# cell.net
KiCad netlist of a schematic drawn in EAGLE
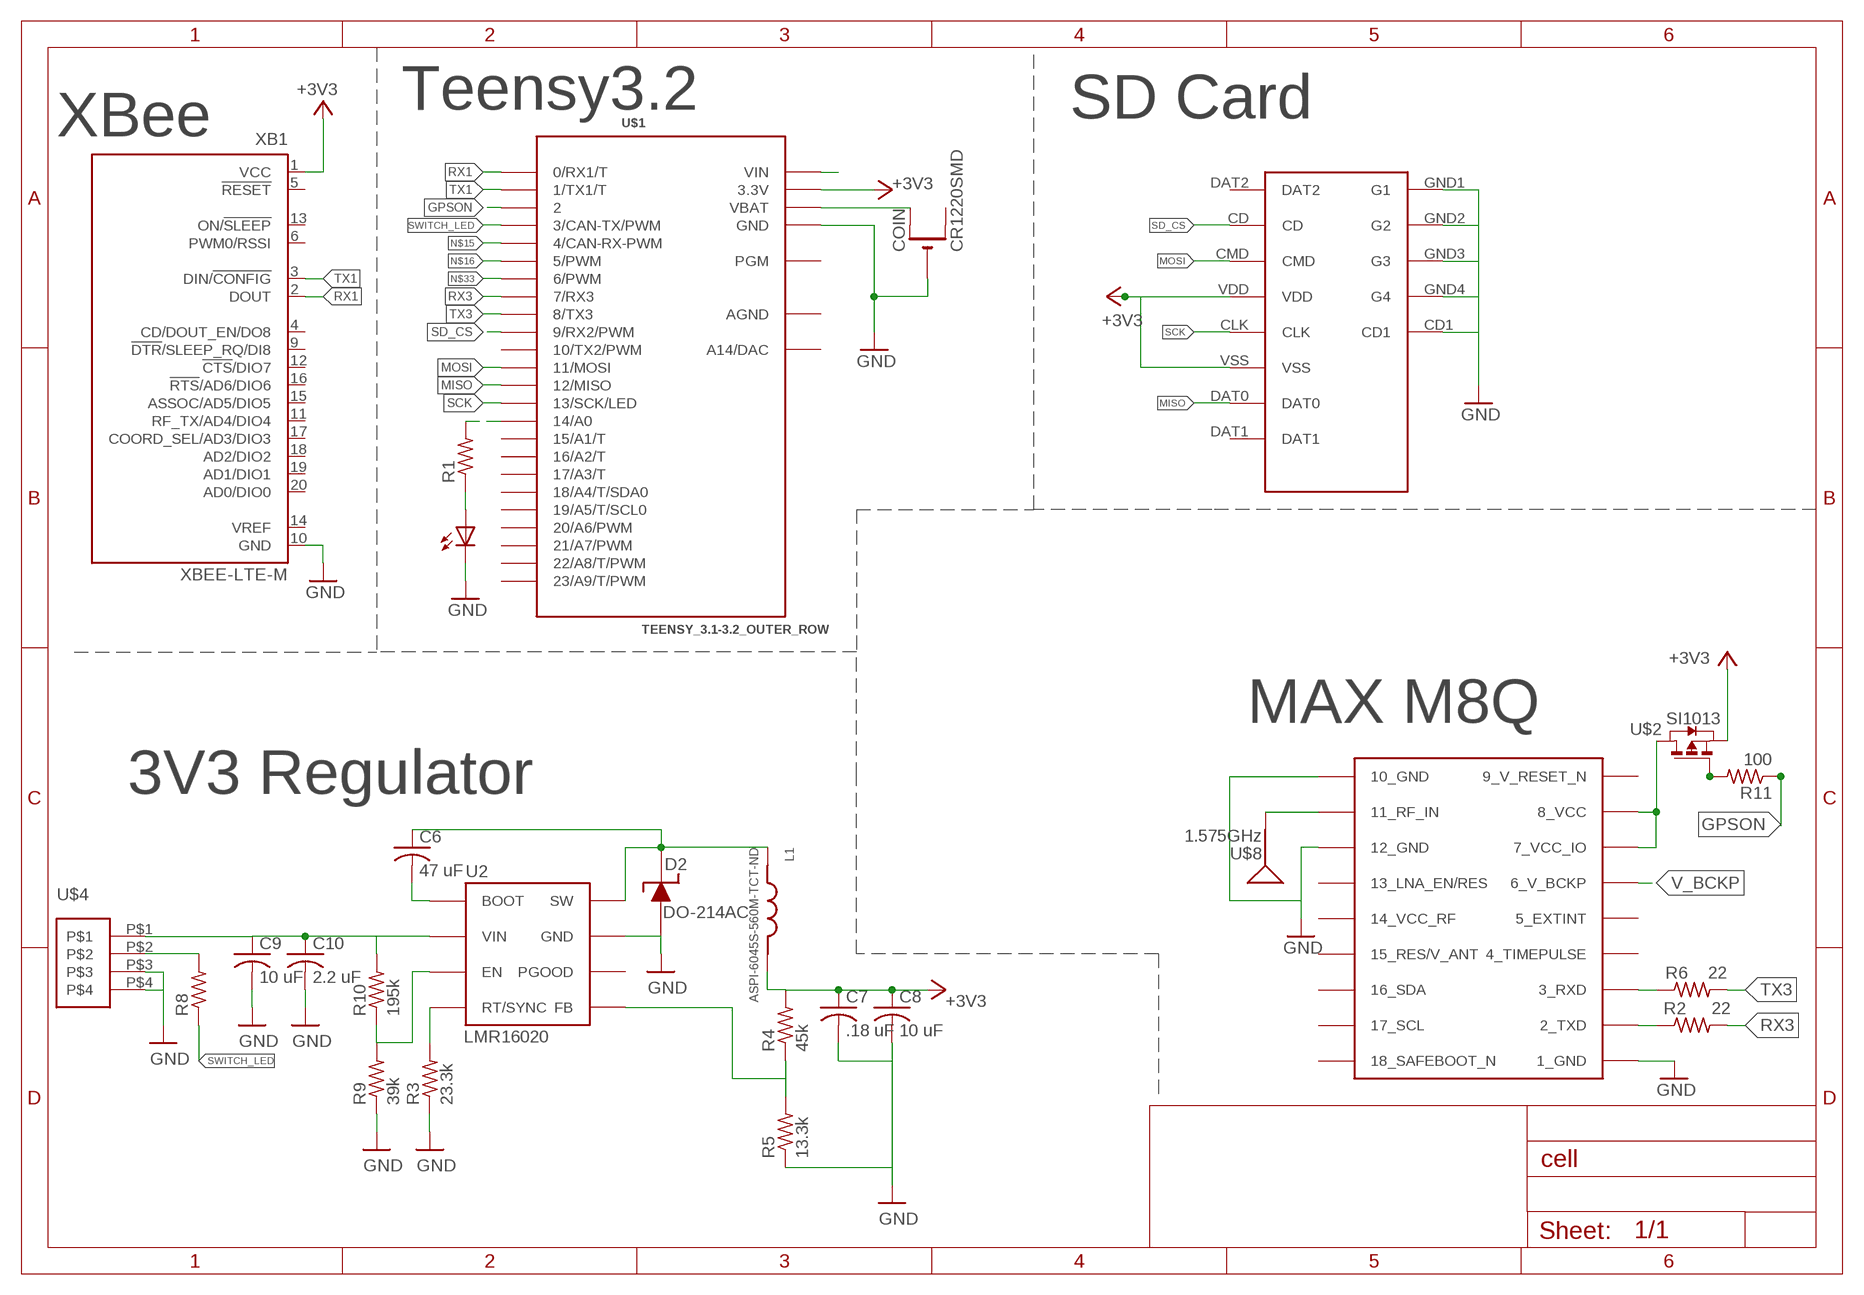
[diagram p0: schematic, sheet 1]

(export (version "E")
  (design (tool "Eeschema 10.0.6"))
  (components
    (comp (ref "C6")
      (value "47 uF")
      (footprint "eagle-import:C0805")
      (libsource (lib "eagle-import") (part "C-USC0805"))
    )
    (comp (ref "C7")
      (value ".18 uF")
      (footprint "eagle-import:C0603")
      (libsource (lib "eagle-import") (part "C-USC0603"))
    )
    (comp (ref "C8")
      (value "10 uF")
      (footprint "eagle-import:C0603")
      (libsource (lib "eagle-import") (part "C-USC0603"))
    )
    (comp (ref "C9")
      (value "10 uF")
      (footprint "eagle-import:C1210")
      (libsource (lib "eagle-import") (part "C-USC1210"))
    )
    (comp (ref "C10")
      (value "2.2 uF")
      (footprint "eagle-import:C1210")
      (libsource (lib "eagle-import") (part "C-USC1210"))
    )
    (comp (ref "COIN")
      (value "CR1220SMD")
      (footprint "eagle-import:CR1220-SMD")
      (libsource (lib "eagle-import") (part "CR1220SMT"))
    )
    (comp (ref "D2")
      (value "DO-214AC")
      (footprint "eagle-import:DO-214AC")
      (libsource (lib "eagle-import") (part "DO-214AC"))
    )
    (comp (ref "L1")
      (value "ASPI-6045S-560M-TCT-ND")
      (footprint "eagle-import:ABRACON")
      (libsource (lib "eagle-import") (part "ASPI-6045S-560M-TCT-ND"))
    )
    (comp (ref "LED1")
      (value "Green")
      (footprint "eagle-import:CHIP-LED0603")
      (libsource (lib "eagle-import") (part "LEDCHIP-LED0603"))
    )
    (comp (ref "R1")
      (value "470")
      (footprint "eagle-import:R0603")
      (libsource (lib "eagle-import") (part "resistor_R-US_R0603"))
    )
    (comp (ref "R2")
      (value "22")
      (footprint "eagle-import:R0603")
      (libsource (lib "eagle-import") (part "R-US_R0603"))
    )
    (comp (ref "R3")
      (value "23.3k")
      (footprint "eagle-import:R0603")
      (libsource (lib "eagle-import") (part "resistor_R-US_R0603"))
    )
    (comp (ref "R4")
      (value "45k")
      (footprint "eagle-import:R0603")
      (libsource (lib "eagle-import") (part "resistor_R-US_R0603"))
    )
    (comp (ref "R5")
      (value "13.3k")
      (footprint "eagle-import:R0603")
      (libsource (lib "eagle-import") (part "resistor_R-US_R0603"))
    )
    (comp (ref "R6")
      (value "22")
      (footprint "eagle-import:R0603")
      (libsource (lib "eagle-import") (part "R-US_R0603"))
    )
    (comp (ref "R8")
      (value "R-US_R0603")
      (footprint "eagle-import:R0603")
      (libsource (lib "eagle-import") (part "resistor_R-US_R0603"))
    )
    (comp (ref "R9")
      (value "39k")
      (footprint "eagle-import:R0603")
      (libsource (lib "eagle-import") (part "resistor_R-US_R0603"))
    )
    (comp (ref "R10")
      (value "195k")
      (footprint "eagle-import:R0603")
      (libsource (lib "eagle-import") (part "resistor_R-US_R0603"))
    )
    (comp (ref "R11")
      (value "100")
      (footprint "eagle-import:R0603")
      (libsource (lib "eagle-import") (part "R-US_R0603"))
    )
    (comp (ref "U$1")
      (value "TEENSY_3.1-3.2_OUTER_ROW")
      (footprint "eagle-import:TEENSY_3.0-3.2&LC_OUTER_ROW")
      (libsource (lib "eagle-import") (part "TEENSY_3.1-3.2_OUTER_ROW"))
    )
    (comp (ref "U$2")
      (value "SI1013")
      (footprint "eagle-import:SC-75")
      (libsource (lib "eagle-import") (part "SI1013"))
    )
    (comp (ref "U$3")
      (value "MICRO_SD")
      (footprint "eagle-import:MICRO_SD_HINGED")
      (libsource (lib "eagle-import") (part "MICRO_SD"))
    )
    (comp (ref "U$4")
      (value "MICROCLASP_4")
      (footprint "eagle-import:4_PIN_MICROCLASP")
      (libsource (lib "eagle-import") (part "MICROCLASP_4"))
    )
    (comp (ref "U$7")
      (value "MAX-M8")
      (footprint "eagle-import:MAX-M8")
      (libsource (lib "eagle-import") (part "MAX-M8"))
    )
    (comp (ref "U$8")
      (value "1.575GHz")
      (footprint "eagle-import:SPARKFUN-GPS_ANT-GPS-2X7MM")
      (libsource (lib "eagle-import") (part "SPARKFUN-GPS_ANTENNAGPS-2X7MM"))
    )
    (comp (ref "U2")
      (value "LMR16020")
      (footprint "eagle-import:SO8")
      (libsource (lib "eagle-import") (part "LMR16020"))
    )
    (comp (ref "XB1")
      (value "XBEE-LTE-M")
      (footprint "eagle-import:XBEE-PRO")
      (fields (field (name "MPN") "XBP24-AWI-001"))
      (libsource (lib "eagle-import") (part "XBEE-PRO"))
    )
  )
  (nets
    (net (code "1") (name "+3V3") (class "Default")
      (node (ref "C7") (pin "1") (pinfunction "1_1") (pintype "passive"))
      (node (ref "C8") (pin "1") (pinfunction "1_1") (pintype "passive"))
      (node (ref "L1") (pin "P$2") (pinfunction "P$2_P$2") (pintype "bidirectional"))
      (node (ref "R4") (pin "2") (pinfunction "2_2") (pintype "passive"))
      (node (ref "U$1") (pin "3.3V") (pinfunction "3.3V_3.3V") (pintype "power_in"))
      (node (ref "U$1") (pin "3.3V1") (pinfunction "3.3V_3.3V1") (pintype "power_in"))
      (node (ref "U$2") (pin "P$2") (pinfunction "S_P$2") (pintype "passive"))
      (node (ref "U$3") (pin "VDD") (pinfunction "VDD_VDD") (pintype "bidirectional"))
      (node (ref "U$3") (pin "VSS") (pinfunction "VSS_VSS") (pintype "bidirectional"))
      (node (ref "XB1") (pin "1") (pinfunction "VCC_1") (pintype "power_in"))
    )
    (net (code "2") (name "/9_V_RESET_N") (class "Default")
      (node (ref "U$7") (pin "9_RESET_N") (pinfunction "9_V_RESET_N_9_RESET_N") (pintype "power_in"))
    )
    (net (code "3") (name "/AGND") (class "Default")
      (node (ref "U$1") (pin "AGND") (pinfunction "AGND_AGND") (pintype "power_in"))
    )
    (net (code "4") (name "GND") (class "Default")
      (node (ref "C10") (pin "2") (pinfunction "2_2") (pintype "passive"))
      (node (ref "C7") (pin "2") (pinfunction "2_2") (pintype "passive"))
      (node (ref "C8") (pin "2") (pinfunction "2_2") (pintype "passive"))
      (node (ref "C9") (pin "2") (pinfunction "2_2") (pintype "passive"))
      (node (ref "COIN") (pin "-") (pinfunction "-_-") (pintype "passive"))
      (node (ref "D2") (pin "P$1") (pinfunction "P$1_P$1") (pintype "bidirectional"))
      (node (ref "LED1") (pin "C") (pinfunction "C_C") (pintype "passive"))
      (node (ref "R3") (pin "1") (pinfunction "1_1") (pintype "passive"))
      (node (ref "R5") (pin "1") (pinfunction "1_1") (pintype "passive"))
      (node (ref "R9") (pin "1") (pinfunction "1_1") (pintype "passive"))
      (node (ref "U$1") (pin "GND") (pinfunction "GND_GND") (pintype "power_in"))
      (node (ref "U$1") (pin "GND1") (pinfunction "GND_GND1") (pintype "power_in"))
      (node (ref "U$3") (pin "CD1") (pinfunction "CD1_CD1") (pintype "bidirectional"))
      (node (ref "U$3") (pin "GND1") (pinfunction "G1_GND1") (pintype "bidirectional"))
      (node (ref "U$3") (pin "GND2") (pinfunction "G2_GND2") (pintype "bidirectional"))
      (node (ref "U$3") (pin "GND3") (pinfunction "G3_GND3") (pintype "bidirectional"))
      (node (ref "U$3") (pin "GND4") (pinfunction "G4_GND4") (pintype "bidirectional"))
      (node (ref "U$4") (pin "P$3") (pinfunction "P$3_P$3") (pintype "bidirectional"))
      (node (ref "U$4") (pin "P$4") (pinfunction "P$4_P$4") (pintype "bidirectional"))
      (node (ref "U$7") (pin "10_GND") (pinfunction "10_GND_10_GND") (pintype "power_in"))
      (node (ref "U$7") (pin "12_GND") (pinfunction "12_GND_12_GND") (pintype "power_in"))
      (node (ref "U$7") (pin "1_GND") (pinfunction "1_GND_1_GND") (pintype "power_in"))
      (node (ref "U2") (pin "P$7") (pinfunction "GND_P$7") (pintype "bidirectional"))
      (node (ref "U2") (pin "PAD") (pinfunction "GND_PAD") (pintype "bidirectional"))
      (node (ref "XB1") (pin "10") (pinfunction "GND_10") (pintype "power_in"))
    )
    (net (code "5") (name "GPSON") (class "Default")
      (node (ref "R11") (pin "1") (pinfunction "1_1") (pintype "passive"))
      (node (ref "U$1") (pin "2") (pinfunction "2_2") (pintype "bidirectional"))
    )
    (net (code "6") (name "MISO") (class "Default")
      (node (ref "U$1") (pin "12") (pinfunction "12/MISO_12") (pintype "bidirectional"))
      (node (ref "U$3") (pin "DAT0") (pinfunction "DAT0_DAT0") (pintype "bidirectional"))
    )
    (net (code "7") (name "MOSI") (class "Default")
      (node (ref "U$1") (pin "11") (pinfunction "11/MOSI_11") (pintype "bidirectional"))
      (node (ref "U$3") (pin "CMD") (pinfunction "CMD_CMD") (pintype "bidirectional"))
    )
    (net (code "8") (name "N$15") (class "Default")
      (node (ref "U$1") (pin "4") (pinfunction "4/CAN-RX-PWM_4") (pintype "bidirectional"))
    )
    (net (code "9") (name "N$16") (class "Default")
      (node (ref "U$1") (pin "5") (pinfunction "5/PWM_5") (pintype "bidirectional"))
    )
    (net (code "10") (name "N$33") (class "Default")
      (node (ref "U$1") (pin "6") (pinfunction "6/PWM_6") (pintype "bidirectional"))
    )
    (net (code "11") (name "Net-(LED1-PadA)") (class "Default")
      (node (ref "LED1") (pin "A") (pinfunction "A_A") (pintype "passive"))
      (node (ref "R1") (pin "1") (pinfunction "1_1") (pintype "passive"))
    )
    (net (code "12") (name "Net-(R1-Pad2)") (class "Default")
      (node (ref "R1") (pin "2") (pinfunction "2_2") (pintype "passive"))
      (node (ref "U$1") (pin "14/A0") (pinfunction "14/A0_14/A0") (pintype "bidirectional"))
    )
    (net (code "13") (name "Net-(R2-Pad1)") (class "Default")
      (node (ref "R2") (pin "1") (pinfunction "1_1") (pintype "passive"))
      (node (ref "U$7") (pin "2_TXD") (pinfunction "2_TXD_2_TXD") (pintype "bidirectional"))
    )
    (net (code "14") (name "Net-(R6-Pad1)") (class "Default")
      (node (ref "R6") (pin "1") (pinfunction "1_1") (pintype "passive"))
      (node (ref "U$7") (pin "3_RXD") (pinfunction "3_RXD_3_RXD") (pintype "bidirectional"))
    )
    (net (code "15") (name "Net-(R8-Pad2)") (class "Default")
      (node (ref "R8") (pin "2") (pinfunction "2_2") (pintype "passive"))
      (node (ref "U$4") (pin "P$2") (pinfunction "P$2_P$2") (pintype "bidirectional"))
    )
    (net (code "16") (name "Net-(U$2-D)") (class "Default")
      (node (ref "U$2") (pin "P$3") (pinfunction "D_P$3") (pintype "passive"))
      (node (ref "U$7") (pin "7_VCC_IO") (pinfunction "7_VCC_IO_7_VCC_IO") (pintype "power_in"))
      (node (ref "U$7") (pin "8_VCC") (pinfunction "8_VCC_8_VCC") (pintype "power_in"))
    )
    (net (code "17") (name "Net-(U$2-G)") (class "Default")
      (node (ref "R11") (pin "2") (pinfunction "2_2") (pintype "passive"))
      (node (ref "U$2") (pin "P$1") (pinfunction "G_P$1") (pintype "passive"))
    )
    (net (code "18") (name "Net-(U$8-SIGNAL)") (class "Default")
      (node (ref "U$7") (pin "11_RF_IN") (pinfunction "11_RF_IN_11_RF_IN") (pintype "bidirectional"))
      (node (ref "U$8") (pin "1") (pinfunction "SIGNAL_1") (pintype "bidirectional"))
    )
    (net (code "19") (name "Net-(U2-BOOT)") (class "Default")
      (node (ref "C6") (pin "2") (pinfunction "2_2") (pintype "passive"))
      (node (ref "U2") (pin "P$1") (pinfunction "BOOT_P$1") (pintype "bidirectional"))
    )
    (net (code "20") (name "Net-(U2-EN)") (class "Default")
      (node (ref "R10") (pin "1") (pinfunction "1_1") (pintype "passive"))
      (node (ref "R9") (pin "2") (pinfunction "2_2") (pintype "passive"))
      (node (ref "U2") (pin "P$3") (pinfunction "EN_P$3") (pintype "bidirectional"))
    )
    (net (code "21") (name "Net-(U2-FB)") (class "Default")
      (node (ref "R4") (pin "1") (pinfunction "1_1") (pintype "passive"))
      (node (ref "R5") (pin "2") (pinfunction "2_2") (pintype "passive"))
      (node (ref "U2") (pin "P$5") (pinfunction "FB_P$5") (pintype "bidirectional"))
    )
    (net (code "22") (name "Net-(U2-RT{slash}SYNC)") (class "Default")
      (node (ref "R3") (pin "2") (pinfunction "2_2") (pintype "passive"))
      (node (ref "U2") (pin "P$4") (pinfunction "RT/SYNC_P$4") (pintype "bidirectional"))
    )
    (net (code "23") (name "Net-(U2-SW)") (class "Default")
      (node (ref "C6") (pin "1") (pinfunction "1_1") (pintype "passive"))
      (node (ref "D2") (pin "P$2") (pinfunction "P$2_P$2") (pintype "bidirectional"))
      (node (ref "L1") (pin "P$1") (pinfunction "P$1_P$1") (pintype "bidirectional"))
      (node (ref "U2") (pin "P$8") (pinfunction "SW_P$8") (pintype "bidirectional"))
    )
    (net (code "24") (name "Net-(U2-VIN)") (class "Default")
      (node (ref "C10") (pin "1") (pinfunction "1_1") (pintype "passive"))
      (node (ref "C9") (pin "1") (pinfunction "1_1") (pintype "passive"))
      (node (ref "R10") (pin "2") (pinfunction "2_2") (pintype "passive"))
      (node (ref "U$4") (pin "P$1") (pinfunction "P$1_P$1") (pintype "bidirectional"))
      (node (ref "U2") (pin "P$2") (pinfunction "VIN_P$2") (pintype "bidirectional"))
    )
    (net (code "25") (name "RX1") (class "Default")
      (node (ref "U$1") (pin "0") (pinfunction "0/RX1/T_0") (pintype "bidirectional"))
      (node (ref "XB1") (pin "2") (pinfunction "DOUT_2") (pintype "output"))
    )
    (net (code "26") (name "RX3") (class "Default")
      (node (ref "R2") (pin "2") (pinfunction "2_2") (pintype "passive"))
      (node (ref "U$1") (pin "7") (pinfunction "7/RX3_7") (pintype "bidirectional"))
    )
    (net (code "27") (name "SCK") (class "Default")
      (node (ref "U$1") (pin "13") (pinfunction "13/SCK/LED_13") (pintype "bidirectional"))
      (node (ref "U$3") (pin "CLK") (pinfunction "CLK_CLK") (pintype "bidirectional"))
    )
    (net (code "28") (name "SD_CS") (class "Default")
      (node (ref "U$1") (pin "9") (pinfunction "9/RX2/PWM_9") (pintype "bidirectional"))
      (node (ref "U$3") (pin "CD") (pinfunction "CD_CD") (pintype "bidirectional"))
    )
    (net (code "29") (name "SWITCH_LED") (class "Default")
      (node (ref "R8") (pin "1") (pinfunction "1_1") (pintype "passive"))
      (node (ref "U$1") (pin "3") (pinfunction "3/CAN-TX/PWM_3") (pintype "bidirectional"))
    )
    (net (code "30") (name "TX1") (class "Default")
      (node (ref "U$1") (pin "1") (pinfunction "1/TX1/T_1") (pintype "bidirectional"))
      (node (ref "XB1") (pin "3") (pinfunction "DIN/~{CONFIG}_3") (pintype "input"))
    )
    (net (code "31") (name "TX3") (class "Default")
      (node (ref "R6") (pin "2") (pinfunction "2_2") (pintype "passive"))
      (node (ref "U$1") (pin "8") (pinfunction "8/TX3_8") (pintype "bidirectional"))
    )
    (net (code "32") (name "V_BCKP") (class "Default")
      (node (ref "COIN") (pin "+$1") (pinfunction "+_+$1") (pintype "passive"))
      (node (ref "U$1") (pin "VBAT") (pinfunction "VBAT_VBAT") (pintype "power_in"))
      (node (ref "U$7") (pin "6_V_BCKP") (pinfunction "6_V_BCKP_6_V_BCKP") (pintype "bidirectional"))
    )
    (net (code "33") (name "unconnected-(COIN-+1-Pad+$2)") (class "Default")
      (node (ref "COIN") (pin "+$2") (pinfunction "+1_+$2") (pintype "passive"))
    )
    (net (code "34") (name "unconnected-(U$1-10{slash}TX2{slash}PWM-Pad10)") (class "Default")
      (node (ref "U$1") (pin "10") (pinfunction "10/TX2/PWM_10") (pintype "bidirectional"))
    )
    (net (code "35") (name "unconnected-(U$1-15{slash}A1{slash}T-Pad15{slash}A1)") (class "Default")
      (node (ref "U$1") (pin "15/A1") (pinfunction "15/A1/T_15/A1") (pintype "bidirectional"))
    )
    (net (code "36") (name "unconnected-(U$1-16{slash}A2{slash}T-Pad16{slash}A2)") (class "Default")
      (node (ref "U$1") (pin "16/A2") (pinfunction "16/A2/T_16/A2") (pintype "bidirectional"))
    )
    (net (code "37") (name "unconnected-(U$1-17{slash}A3{slash}T-Pad17{slash}A3)") (class "Default")
      (node (ref "U$1") (pin "17/A3") (pinfunction "17/A3/T_17/A3") (pintype "bidirectional"))
    )
    (net (code "38") (name "unconnected-(U$1-18{slash}A4{slash}T{slash}SDA0-Pad18{slash}A4)") (class "Default")
      (node (ref "U$1") (pin "18/A4") (pinfunction "18/A4/T/SDA0_18/A4") (pintype "bidirectional"))
    )
    (net (code "39") (name "unconnected-(U$1-19{slash}A5{slash}T{slash}SCL0-Pad19{slash}A5)") (class "Default")
      (node (ref "U$1") (pin "19/A5") (pinfunction "19/A5/T/SCL0_19/A5") (pintype "bidirectional"))
    )
    (net (code "40") (name "unconnected-(U$1-20{slash}A6{slash}PWM-Pad20{slash}A6)") (class "Default")
      (node (ref "U$1") (pin "20/A6") (pinfunction "20/A6/PWM_20/A6") (pintype "bidirectional"))
    )
    (net (code "41") (name "unconnected-(U$1-21{slash}A7{slash}PWM-Pad21{slash}A7)") (class "Default")
      (node (ref "U$1") (pin "21/A7") (pinfunction "21/A7/PWM_21/A7") (pintype "bidirectional"))
    )
    (net (code "42") (name "unconnected-(U$1-22{slash}A8{slash}T{slash}PWM-Pad22{slash}A8)") (class "Default")
      (node (ref "U$1") (pin "22/A8") (pinfunction "22/A8/T/PWM_22/A8") (pintype "bidirectional"))
    )
    (net (code "43") (name "unconnected-(U$1-23{slash}A9{slash}T{slash}PWM-Pad23{slash}A9)") (class "Default")
      (node (ref "U$1") (pin "23/A9") (pinfunction "23/A9/T/PWM_23/A9") (pintype "bidirectional"))
    )
    (net (code "44") (name "unconnected-(U$1-A14{slash}DAC-PadRESET{slash}DAC)") (class "Default")
      (node (ref "U$1") (pin "RESET/DAC") (pinfunction "A14/DAC_RESET/DAC") (pintype "bidirectional"))
    )
    (net (code "45") (name "unconnected-(U$1-PadPGM)") (class "Default")
      (node (ref "U$1") (pin "PGM") (pinfunction "PGM_PGM") (pintype "bidirectional"))
    )
    (net (code "46") (name "unconnected-(U$1-PadVIN)") (class "Default")
      (node (ref "U$1") (pin "VIN") (pinfunction "VIN_VIN") (pintype "power_in"))
    )
    (net (code "47") (name "unconnected-(U$3-PadDAT1)") (class "Default")
      (node (ref "U$3") (pin "DAT1") (pinfunction "DAT1_DAT1") (pintype "bidirectional"))
    )
    (net (code "48") (name "unconnected-(U$3-PadDAT2)") (class "Default")
      (node (ref "U$3") (pin "DAT2") (pinfunction "DAT2_DAT2") (pintype "bidirectional"))
    )
    (net (code "49") (name "unconnected-(U$7-13_LNA_EN{slash}RES-Pad13_LNA_EN)") (class "Default")
      (node (ref "U$7") (pin "13_LNA_EN") (pinfunction "13_LNA_EN/RES_13_LNA_EN") (pintype "bidirectional"))
    )
    (net (code "50") (name "unconnected-(U$7-15_RES{slash}V_ANT-Pad15_V_ANT{slash}RESERVED)") (class "Default")
      (node (ref "U$7") (pin "15_V_ANT/RESERVED") (pinfunction "15_RES/V_ANT_15_V_ANT/RESERVED") (pintype "bidirectional"))
    )
    (net (code "51") (name "unconnected-(U$7-Pad4_TIMEPULSE)") (class "Default")
      (node (ref "U$7") (pin "4_TIMEPULSE") (pinfunction "4_TIMEPULSE_4_TIMEPULSE") (pintype "bidirectional"))
    )
    (net (code "52") (name "unconnected-(U$7-Pad5_EXTINT)") (class "Default")
      (node (ref "U$7") (pin "5_EXTINT") (pinfunction "5_EXTINT_5_EXTINT") (pintype "bidirectional"))
    )
    (net (code "53") (name "unconnected-(U$7-Pad14_VCC_RF)") (class "Default")
      (node (ref "U$7") (pin "14_VCC_RF") (pinfunction "14_VCC_RF_14_VCC_RF") (pintype "bidirectional"))
    )
    (net (code "54") (name "unconnected-(U$7-Pad16_SDA)") (class "Default")
      (node (ref "U$7") (pin "16_SDA") (pinfunction "16_SDA_16_SDA") (pintype "bidirectional"))
    )
    (net (code "55") (name "unconnected-(U$7-Pad17_SCL)") (class "Default")
      (node (ref "U$7") (pin "17_SCL") (pinfunction "17_SCL_17_SCL") (pintype "bidirectional"))
    )
    (net (code "56") (name "unconnected-(U$7-Pad18_SAFEBOOT_N)") (class "Default")
      (node (ref "U$7") (pin "18_SAFEBOOT_N") (pinfunction "18_SAFEBOOT_N_18_SAFEBOOT_N") (pintype "bidirectional"))
    )
    (net (code "57") (name "unconnected-(U2-PGOOD-PadP$6)") (class "Default")
      (node (ref "U2") (pin "P$6") (pinfunction "PGOOD_P$6") (pintype "bidirectional"))
    )
    (net (code "58") (name "unconnected-(XB1-AD0{slash}DIO0-Pad20)") (class "Default")
      (node (ref "XB1") (pin "20") (pinfunction "AD0/DIO0_20") (pintype "bidirectional"))
    )
    (net (code "59") (name "unconnected-(XB1-AD1{slash}DIO1-Pad19)") (class "Default")
      (node (ref "XB1") (pin "19") (pinfunction "AD1/DIO1_19") (pintype "bidirectional"))
    )
    (net (code "60") (name "unconnected-(XB1-AD2{slash}DIO2-Pad18)") (class "Default")
      (node (ref "XB1") (pin "18") (pinfunction "AD2/DIO2_18") (pintype "bidirectional"))
    )
    (net (code "61") (name "unconnected-(XB1-ASSOC{slash}AD5{slash}DIO5-Pad15)") (class "Default")
      (node (ref "XB1") (pin "15") (pinfunction "ASSOC/AD5/DIO5_15") (pintype "bidirectional"))
    )
    (net (code "62") (name "unconnected-(XB1-CD{slash}DOUT_EN{slash}DO8-Pad4)") (class "Default")
      (node (ref "XB1") (pin "4") (pinfunction "CD/DOUT_EN/DO8_4") (pintype "output"))
    )
    (net (code "63") (name "unconnected-(XB1-COORD_SEL{slash}AD3{slash}DIO3-Pad17)") (class "Default")
      (node (ref "XB1") (pin "17") (pinfunction "COORD_SEL/AD3/DIO3_17") (pintype "bidirectional"))
    )
    (net (code "64") (name "unconnected-(XB1-ON{slash}~{SLEEP}-Pad13)") (class "Default")
      (node (ref "XB1") (pin "13") (pinfunction "ON/~{SLEEP}_13") (pintype "output"))
    )
    (net (code "65") (name "unconnected-(XB1-PWM0{slash}RSSI-Pad6)") (class "Default")
      (node (ref "XB1") (pin "6") (pinfunction "PWM0/RSSI_6") (pintype "output"))
    )
    (net (code "66") (name "unconnected-(XB1-RF_TX{slash}AD4{slash}DIO4-Pad11)") (class "Default")
      (node (ref "XB1") (pin "11") (pinfunction "RF_TX/AD4/DIO4_11") (pintype "bidirectional"))
    )
    (net (code "67") (name "unconnected-(XB1-VREF-Pad14)") (class "Default")
      (node (ref "XB1") (pin "14") (pinfunction "VREF_14") (pintype "input"))
    )
    (net (code "68") (name "unconnected-(XB1-~{CTS}{slash}DIO7-Pad12)") (class "Default")
      (node (ref "XB1") (pin "12") (pinfunction "~{CTS}/DIO7_12") (pintype "bidirectional"))
    )
    (net (code "69") (name "unconnected-(XB1-~{DTR}{slash}SLEEP_RQ{slash}DI8-Pad9)") (class "Default")
      (node (ref "XB1") (pin "9") (pinfunction "~{DTR}/SLEEP_RQ/DI8_9") (pintype "bidirectional"))
    )
    (net (code "70") (name "unconnected-(XB1-~{RESET}-Pad5)") (class "Default")
      (node (ref "XB1") (pin "5") (pinfunction "~{RESET}_5") (pintype "input"))
    )
    (net (code "71") (name "unconnected-(XB1-~{RTS}{slash}AD6{slash}DIO6-Pad16)") (class "Default")
      (node (ref "XB1") (pin "16") (pinfunction "~{RTS}/AD6/DIO6_16") (pintype "bidirectional"))
    )
  )
)
